# Sheet1.net
KiCad netlist of a schematic drawn in Altium Designer
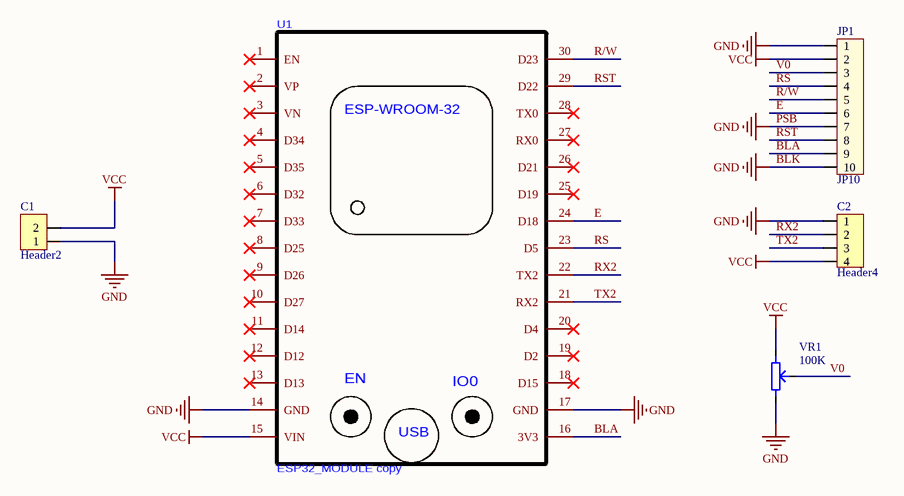
[diagram p0: Sheet1.SchDoc]

(export (version "E")
  (design (tool "Eeschema 10.0.6"))
  (components
    (comp (ref "C1")
      (value "Header2")
      (footprint "Header2")
      (description "Header IDC, 2 x 1 Pin Vertical 2.54mm Pitch (Non-Boxed, Male)")
      (fields
        (field (name "MANUFACTURER") "Würth Elektronik eiSos GmbH")
        (field (name "PARTNO") "613002143121")
        (field (name "CREATED BY") "Karrer Zheng")
      )
      (libsource (lib "myLib_v1") (part "Header2"))
    )
    (comp (ref "C2")
      (value "Header4")
      (footprint "Header4")
      (description "Header IDC, 4 x 1 Pin Vertical 2.54mm Pitch (Non-Boxed, Male)")
      (fields
        (field (name "MANUFACTURER") "Würth Elektronik eiSos GmbH")
        (field (name "PARTNO") "613002143121")
        (field (name "CREATED BY") "Karrer Zheng")
      )
      (libsource (lib "myLib_v1") (part "Header4"))
    )
    (comp (ref "JP1")
      (value "JP10")
      (footprint "Header10")
      (description "Connector 10")
      (libsource (lib "myLib_v1") (part "Header10"))
    )
    (comp (ref "U1")
      (value "ESP32_MODULE copy")
      (footprint "ESP32-WIFIMODULE-FOOTPRINT")
      (libsource (lib "myLib_v1") (part "ESP32_MODULE copy"))
    )
    (comp (ref "VR1")
      (value "100K")
      (footprint "Bien Tro Tam Giac Dung")
      (description "Cắm")
      (libsource (lib "Altium_Lib_by_KhueNguyenCreator") (part "Bien tro tam giac 100K Dung"))
    )
  )
  (nets
    (net (code "1") (name "/BLA") (class "Default")
      (node (ref "JP1") (pin "9") (pinfunction "9_9") (pintype "passive"))
      (node (ref "U1") (pin "16") (pinfunction "3V3_16") (pintype "passive"))
    )
    (net (code "2") (name "/E") (class "Default")
      (node (ref "JP1") (pin "6") (pinfunction "6_6") (pintype "passive"))
      (node (ref "U1") (pin "24") (pinfunction "D18_24") (pintype "passive"))
    )
    (net (code "3") (name "/RS") (class "Default")
      (node (ref "JP1") (pin "4") (pinfunction "4_4") (pintype "passive"))
      (node (ref "U1") (pin "23") (pinfunction "D5_23") (pintype "passive"))
    )
    (net (code "4") (name "/RST") (class "Default")
      (node (ref "JP1") (pin "8") (pinfunction "8_8") (pintype "passive"))
      (node (ref "U1") (pin "29") (pinfunction "D22_29") (pintype "passive"))
    )
    (net (code "5") (name "/RX2") (class "Default")
      (node (ref "C2") (pin "2") (pinfunction "2_2") (pintype "passive"))
      (node (ref "U1") (pin "22") (pinfunction "TX2_22") (pintype "passive"))
    )
    (net (code "6") (name "/R{slash}W") (class "Default")
      (node (ref "JP1") (pin "5") (pinfunction "5_5") (pintype "passive"))
      (node (ref "U1") (pin "30") (pinfunction "D23_30") (pintype "passive"))
    )
    (net (code "7") (name "/TX2") (class "Default")
      (node (ref "C2") (pin "3") (pinfunction "3_3") (pintype "passive"))
      (node (ref "U1") (pin "21") (pinfunction "RX2_21") (pintype "passive"))
    )
    (net (code "8") (name "/V0") (class "Default")
      (node (ref "JP1") (pin "3") (pinfunction "3_3") (pintype "passive"))
      (node (ref "VR1") (pin "2") (pinfunction "2_2") (pintype "passive"))
    )
    (net (code "9") (name "GND") (class "Default")
      (node (ref "C1") (pin "1") (pinfunction "1_1") (pintype "passive"))
      (node (ref "C2") (pin "1") (pinfunction "1_1") (pintype "passive"))
      (node (ref "JP1") (pin "1") (pinfunction "1_1") (pintype "passive"))
      (node (ref "JP1") (pin "10") (pinfunction "10_10") (pintype "passive"))
      (node (ref "JP1") (pin "7") (pinfunction "7_7") (pintype "passive"))
      (node (ref "U1") (pin "14") (pinfunction "GND_14") (pintype "passive"))
      (node (ref "U1") (pin "17") (pinfunction "GND_17") (pintype "passive"))
      (node (ref "VR1") (pin "3") (pinfunction "3_3") (pintype "passive"))
    )
    (net (code "10") (name "VCC") (class "Default")
      (node (ref "C1") (pin "2") (pinfunction "2_2") (pintype "passive"))
      (node (ref "C2") (pin "4") (pinfunction "4_4") (pintype "passive"))
      (node (ref "JP1") (pin "2") (pinfunction "2_2") (pintype "passive"))
      (node (ref "U1") (pin "15") (pinfunction "VIN_15") (pintype "passive"))
      (node (ref "VR1") (pin "1") (pinfunction "1_1") (pintype "passive"))
    )
    (net (code "11") (name "unconnected-(U1-D2-Pad19)") (class "Default")
      (node (ref "U1") (pin "19") (pinfunction "D2_19") (pintype "passive+no_connect"))
    )
    (net (code "12") (name "unconnected-(U1-D4-Pad20)") (class "Default")
      (node (ref "U1") (pin "20") (pinfunction "D4_20") (pintype "passive+no_connect"))
    )
    (net (code "13") (name "unconnected-(U1-D12-Pad12)") (class "Default")
      (node (ref "U1") (pin "12") (pinfunction "D12_12") (pintype "passive+no_connect"))
    )
    (net (code "14") (name "unconnected-(U1-D13-Pad13)") (class "Default")
      (node (ref "U1") (pin "13") (pinfunction "D13_13") (pintype "passive+no_connect"))
    )
    (net (code "15") (name "unconnected-(U1-D14-Pad11)") (class "Default")
      (node (ref "U1") (pin "11") (pinfunction "D14_11") (pintype "passive+no_connect"))
    )
    (net (code "16") (name "unconnected-(U1-D15-Pad18)") (class "Default")
      (node (ref "U1") (pin "18") (pinfunction "D15_18") (pintype "passive+no_connect"))
    )
    (net (code "17") (name "unconnected-(U1-D19-Pad25)") (class "Default")
      (node (ref "U1") (pin "25") (pinfunction "D19_25") (pintype "passive+no_connect"))
    )
    (net (code "18") (name "unconnected-(U1-D21-Pad26)") (class "Default")
      (node (ref "U1") (pin "26") (pinfunction "D21_26") (pintype "passive+no_connect"))
    )
    (net (code "19") (name "unconnected-(U1-D25-Pad8)") (class "Default")
      (node (ref "U1") (pin "8") (pinfunction "D25_8") (pintype "passive+no_connect"))
    )
    (net (code "20") (name "unconnected-(U1-D26-Pad9)") (class "Default")
      (node (ref "U1") (pin "9") (pinfunction "D26_9") (pintype "passive+no_connect"))
    )
    (net (code "21") (name "unconnected-(U1-D27-Pad10)") (class "Default")
      (node (ref "U1") (pin "10") (pinfunction "D27_10") (pintype "passive+no_connect"))
    )
    (net (code "22") (name "unconnected-(U1-D32-Pad6)") (class "Default")
      (node (ref "U1") (pin "6") (pinfunction "D32_6") (pintype "passive+no_connect"))
    )
    (net (code "23") (name "unconnected-(U1-D33-Pad7)") (class "Default")
      (node (ref "U1") (pin "7") (pinfunction "D33_7") (pintype "passive+no_connect"))
    )
    (net (code "24") (name "unconnected-(U1-D34-Pad4)") (class "Default")
      (node (ref "U1") (pin "4") (pinfunction "D34_4") (pintype "passive+no_connect"))
    )
    (net (code "25") (name "unconnected-(U1-D35-Pad5)") (class "Default")
      (node (ref "U1") (pin "5") (pinfunction "D35_5") (pintype "passive+no_connect"))
    )
    (net (code "26") (name "unconnected-(U1-EN-Pad1)") (class "Default")
      (node (ref "U1") (pin "1") (pinfunction "EN_1") (pintype "passive+no_connect"))
    )
    (net (code "27") (name "unconnected-(U1-RX0-Pad27)") (class "Default")
      (node (ref "U1") (pin "27") (pinfunction "RX0_27") (pintype "passive+no_connect"))
    )
    (net (code "28") (name "unconnected-(U1-TX0-Pad28)") (class "Default")
      (node (ref "U1") (pin "28") (pinfunction "TX0_28") (pintype "passive+no_connect"))
    )
    (net (code "29") (name "unconnected-(U1-VN-Pad3)") (class "Default")
      (node (ref "U1") (pin "3") (pinfunction "VN_3") (pintype "passive+no_connect"))
    )
    (net (code "30") (name "unconnected-(U1-VP-Pad2)") (class "Default")
      (node (ref "U1") (pin "2") (pinfunction "VP_2") (pintype "passive+no_connect"))
    )
  )
)
